# 0831.net
KiCad netlist of a schematic drawn in Altium Designer
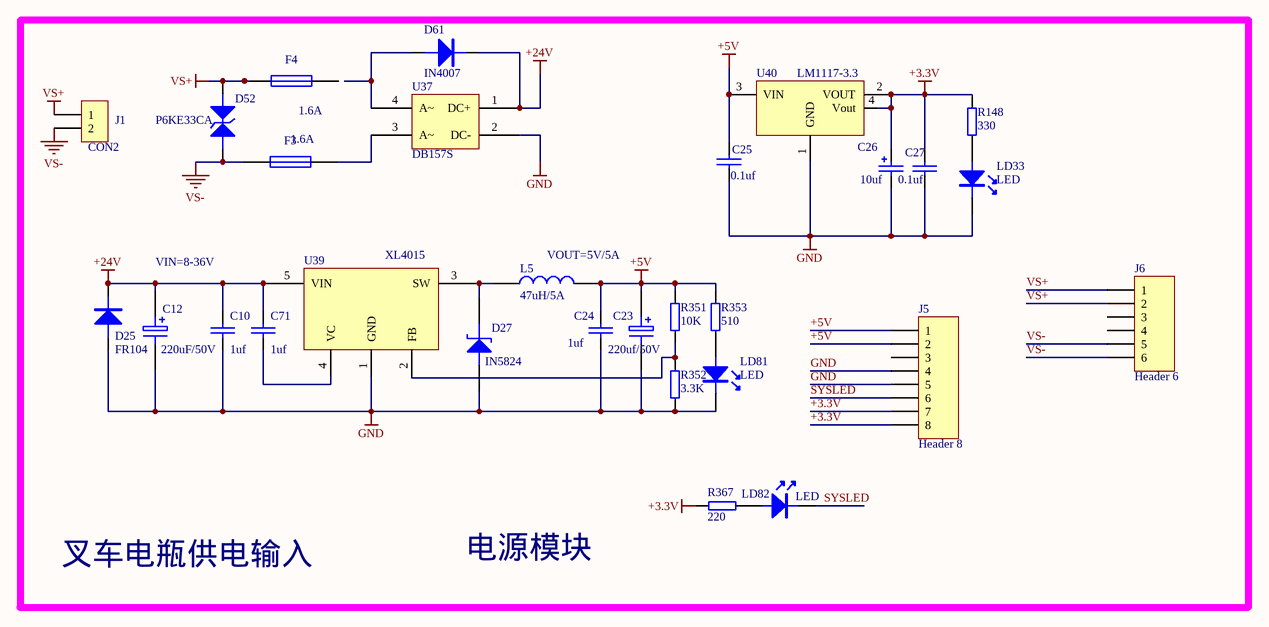
[diagram p0: 如意硬件电源模块0831.SchDoc]

(export (version "E")
  (design (tool "Eeschema 10.0.6"))
  (components
    (comp (ref "C10")
      (value "1uf")
      (footprint "0805-1")
      (description "Capacitor")
      (libsource (lib "*") (part "CAP"))
    )
    (comp (ref "C12")
      (value "220uF/50V")
      (footprint "C-RB-S10")
      (description "Electrolytic Capacitor")
      (libsource (lib "*") (part "ELECTRO1"))
    )
    (comp (ref "C23")
      (value "220uf/50V")
      (footprint "C-RB-S10")
      (description "Electrolytic Capacitor")
      (libsource (lib "*") (part "ELECTRO1"))
    )
    (comp (ref "C24")
      (value "1uf")
      (footprint "0805-1")
      (description "Capacitor")
      (libsource (lib "*") (part "CAP"))
    )
    (comp (ref "C25")
      (value "0.1uf")
      (footprint "0805-1")
      (description "CAP")
      (libsource (lib "*") (part "CAP0"))
    )
    (comp (ref "C26") (value "10uf") (footprint "C-RB-S6") (libsource (lib "*") (part "ECAP")))
    (comp (ref "C27")
      (value "0.1uf")
      (footprint "0805-1")
      (description "CAP")
      (libsource (lib "*") (part "CAP0"))
    )
    (comp (ref "C71")
      (value "1uf")
      (footprint "0805-1")
      (description "Capacitor")
      (libsource (lib "*") (part "CAP"))
    )
    (comp (ref "D25")
      (value "FR104")
      (footprint "DIODETP-5")
      (description "Diode")
      (libsource (lib "*") (part "DIODE"))
    )
    (comp (ref "D27")
      (value "IN5824")
      (footprint "SMB")
      (description "Zener Diode")
      (libsource (lib "*") (part "ZENER2"))
    )
    (comp (ref "D52") (value "P6KE33CA") (footprint "SMB") (libsource (lib "*") (part "TVS")))
    (comp (ref "D61")
      (value "IN4007")
      (footprint "SMB")
      (description "Diode")
      (libsource (lib "*") (part "DIODE"))
    )
    (comp (ref "F3")
      (value "1.6A")
      (footprint "1812")
      (description "Fuse")
      (libsource (lib "*") (part "FUSE1"))
    )
    (comp (ref "F4")
      (value "1.6A")
      (footprint "1812")
      (description "Fuse")
      (libsource (lib "*") (part "FUSE1"))
    )
    (comp (ref "J1")
      (value "CON2")
      (footprint "JK126-2")
      (description "Connector")
      (libsource (lib "*") (part "CON2"))
    )
    (comp (ref "J5")
      (value "Header 8")
      (footprint "HDR1X8")
      (description "Header, 8-Pin")
      (fields (field (name "PUBLISHER") "Altium Limited"))
      (libsource (lib "Miscellaneous Connectors") (part "Header 8"))
    )
    (comp (ref "J6")
      (value "Header 6")
      (footprint "HDR1X6")
      (description "接插件")
      (fields (field (name "PUBLISHER") "Altium Limited"))
      (libsource (lib "Miscellaneous Connectors") (part "Header 6"))
    )
    (comp (ref "L5") (value "47uH/5A") (footprint "L1-47uH/5A") (libsource (lib "*") (part "INDUCTOR")))
    (comp (ref "LD33") (value "LED") (footprint "LED_Z1") (libsource (lib "") (part "LED_1")))
    (comp (ref "LD81") (value "LED") (footprint "LED_Z1") (libsource (lib "") (part "LED_1")))
    (comp (ref "LD82") (value "LED") (footprint "LED_Z1") (libsource (lib "*") (part "LED")))
    (comp (ref "R148") (value "330") (footprint "0805-1") (libsource (lib "*") (part "RES-2")))
    (comp (ref "R351") (value "10K") (footprint "0805-1") (libsource (lib "*") (part "RES-2")))
    (comp (ref "R352") (value "3.3K") (footprint "0805-1") (libsource (lib "*") (part "RES-2")))
    (comp (ref "R353") (value "510") (footprint "0805-1") (libsource (lib "*") (part "RES-2")))
    (comp (ref "R367") (value "220") (footprint "0805-1") (libsource (lib "") (part "RES-2_1")))
    (comp (ref "U37") (value "DB157S") (footprint "SOP-DBS") (libsource (lib "*") (part "MB6S")))
    (comp (ref "U39") (value "XL4015") (footprint "TO-263-5") (libsource (lib "zongruyi") (part "XL4015")))
    (comp (ref "U40") (value "LM1117-3.3") (footprint "ASM1117") (libsource (lib "*") (part "LM1117")))
  )
  (nets
    (net (code "1") (name "+3.3V") (class "Default")
      (node (ref "C26") (pin "1") (pintype "passive"))
      (node (ref "C27") (pin "2") (pintype "passive"))
      (node (ref "J5") (pin "7") (pinfunction "7_7") (pintype "passive"))
      (node (ref "J5") (pin "8") (pinfunction "8_8") (pintype "passive"))
      (node (ref "R148") (pin "1") (pinfunction "1_1") (pintype "passive"))
      (node (ref "R367") (pin "1") (pinfunction "1_1") (pintype "passive"))
      (node (ref "U40") (pin "2") (pinfunction "VOUT_2") (pintype "passive"))
      (node (ref "U40") (pin "4") (pinfunction "Vout_4") (pintype "passive"))
    )
    (net (code "2") (name "+5V") (class "Default")
      (node (ref "C23") (pin "1") (pinfunction "1_1") (pintype "passive"))
      (node (ref "C24") (pin "1") (pinfunction "1_1") (pintype "passive"))
      (node (ref "C25") (pin "2") (pintype "passive"))
      (node (ref "J5") (pin "1") (pinfunction "1_1") (pintype "passive"))
      (node (ref "J5") (pin "2") (pinfunction "2_2") (pintype "passive"))
      (node (ref "L5") (pin "2") (pinfunction "2_2") (pintype "passive"))
      (node (ref "R351") (pin "1") (pinfunction "1_1") (pintype "passive"))
      (node (ref "R353") (pin "1") (pinfunction "1_1") (pintype "passive"))
      (node (ref "U40") (pin "3") (pinfunction "VIN_3") (pintype "passive"))
    )
    (net (code "3") (name "+24V") (class "Default")
      (node (ref "C10") (pin "1") (pinfunction "1_1") (pintype "passive"))
      (node (ref "C12") (pin "1") (pinfunction "1_1") (pintype "passive"))
      (node (ref "C71") (pin "1") (pinfunction "1_1") (pintype "passive"))
      (node (ref "D25") (pin "2") (pinfunction "2_2") (pintype "passive"))
      (node (ref "D61") (pin "2") (pinfunction "2_2") (pintype "passive"))
      (node (ref "U37") (pin "1") (pinfunction "DC+_1") (pintype "passive"))
      (node (ref "U39") (pin "5") (pinfunction "VIN_5") (pintype "passive"))
    )
    (net (code "4") (name "/SYSLED") (class "Default")
      (node (ref "J5") (pin "6") (pinfunction "6_6") (pintype "passive"))
      (node (ref "LD82") (pin "2") (pinfunction "2_2") (pintype "passive"))
    )
    (net (code "5") (name "GND") (class "Default")
      (node (ref "C10") (pin "2") (pinfunction "2_2") (pintype "passive"))
      (node (ref "C12") (pin "2") (pinfunction "2_2") (pintype "passive"))
      (node (ref "C23") (pin "2") (pinfunction "2_2") (pintype "passive"))
      (node (ref "C24") (pin "2") (pinfunction "2_2") (pintype "passive"))
      (node (ref "C25") (pin "1") (pintype "passive"))
      (node (ref "C26") (pin "2") (pintype "passive"))
      (node (ref "C27") (pin "1") (pintype "passive"))
      (node (ref "D25") (pin "1") (pinfunction "1_1") (pintype "passive"))
      (node (ref "D27") (pin "1") (pinfunction "A_1") (pintype "passive"))
      (node (ref "J5") (pin "4") (pinfunction "4_4") (pintype "passive"))
      (node (ref "J5") (pin "5") (pinfunction "5_5") (pintype "passive"))
      (node (ref "LD33") (pin "2") (pinfunction "2_2") (pintype "passive"))
      (node (ref "LD81") (pin "2") (pinfunction "2_2") (pintype "passive"))
      (node (ref "R352") (pin "2") (pinfunction "2_2") (pintype "passive"))
      (node (ref "U37") (pin "2") (pinfunction "DC-_2") (pintype "passive"))
      (node (ref "U39") (pin "1") (pinfunction "GND_1") (pintype "passive"))
      (node (ref "U40") (pin "1") (pinfunction "GND_1") (pintype "passive"))
    )
    (net (code "6") (name "Net-(D27-K)") (class "Default")
      (node (ref "D27") (pin "2") (pinfunction "K_2") (pintype "passive"))
      (node (ref "L5") (pin "1") (pinfunction "1_1") (pintype "passive"))
      (node (ref "U39") (pin "3") (pinfunction "SW_3") (pintype "passive"))
    )
    (net (code "7") (name "Net-(D61-Pad1)") (class "Default")
      (node (ref "D61") (pin "1") (pinfunction "1_1") (pintype "passive"))
      (node (ref "U37") (pin "4") (pinfunction "A~_4") (pintype "passive"))
    )
    (net (code "8") (name "Net-(F3-Pad2)") (class "Default")
      (node (ref "F3") (pin "2") (pinfunction "2_2") (pintype "passive"))
      (node (ref "U37") (pin "3") (pinfunction "A~_3") (pintype "passive"))
    )
    (net (code "9") (name "Net-(LD33-Pad1)") (class "Default")
      (node (ref "LD33") (pin "1") (pinfunction "1_1") (pintype "passive"))
      (node (ref "R148") (pin "2") (pinfunction "2_2") (pintype "passive"))
    )
    (net (code "10") (name "Net-(LD81-Pad1)") (class "Default")
      (node (ref "LD81") (pin "1") (pinfunction "1_1") (pintype "passive"))
      (node (ref "R353") (pin "2") (pinfunction "2_2") (pintype "passive"))
    )
    (net (code "11") (name "Net-(LD82-Pad1)") (class "Default")
      (node (ref "LD82") (pin "1") (pinfunction "1_1") (pintype "passive"))
      (node (ref "R367") (pin "2") (pinfunction "2_2") (pintype "passive"))
    )
    (net (code "12") (name "Net-(U39-FB)") (class "Default")
      (node (ref "R351") (pin "2") (pinfunction "2_2") (pintype "passive"))
      (node (ref "R352") (pin "1") (pinfunction "1_1") (pintype "passive"))
      (node (ref "U39") (pin "2") (pinfunction "FB_2") (pintype "passive"))
    )
    (net (code "13") (name "Net-(U39-VC)") (class "Default")
      (node (ref "C71") (pin "2") (pinfunction "2_2") (pintype "passive"))
      (node (ref "U39") (pin "4") (pinfunction "VC_4") (pintype "passive"))
    )
    (net (code "14") (name "VS+") (class "Default")
      (node (ref "D52") (pin "2") (pinfunction "K_2") (pintype "passive"))
      (node (ref "F4") (pin "1") (pinfunction "1_1") (pintype "passive"))
      (node (ref "J1") (pin "1") (pinfunction "1_1") (pintype "passive"))
      (node (ref "J6") (pin "1") (pinfunction "1_1") (pintype "passive"))
      (node (ref "J6") (pin "2") (pinfunction "2_2") (pintype "passive"))
    )
    (net (code "15") (name "VS-") (class "Default")
      (node (ref "D52") (pin "1") (pinfunction "A_1") (pintype "passive"))
      (node (ref "F3") (pin "1") (pinfunction "1_1") (pintype "passive"))
      (node (ref "J1") (pin "2") (pinfunction "2_2") (pintype "passive"))
      (node (ref "J6") (pin "5") (pinfunction "5_5") (pintype "passive"))
      (node (ref "J6") (pin "6") (pinfunction "6_6") (pintype "passive"))
    )
    (net (code "16") (name "unconnected-(F4-Pad2)") (class "Default")
      (node (ref "F4") (pin "2") (pinfunction "2_2") (pintype "passive"))
    )
    (net (code "17") (name "unconnected-(J5-Pad3)") (class "Default")
      (node (ref "J5") (pin "3") (pinfunction "3_3") (pintype "passive"))
    )
    (net (code "18") (name "unconnected-(J6-Pad3)") (class "Default")
      (node (ref "J6") (pin "3") (pinfunction "3_3") (pintype "passive"))
    )
    (net (code "19") (name "unconnected-(J6-Pad4)") (class "Default")
      (node (ref "J6") (pin "4") (pinfunction "4_4") (pintype "passive"))
    )
  )
)
